# CaravanPi_V3.net
KiCad netlist of a schematic drawn in EAGLE
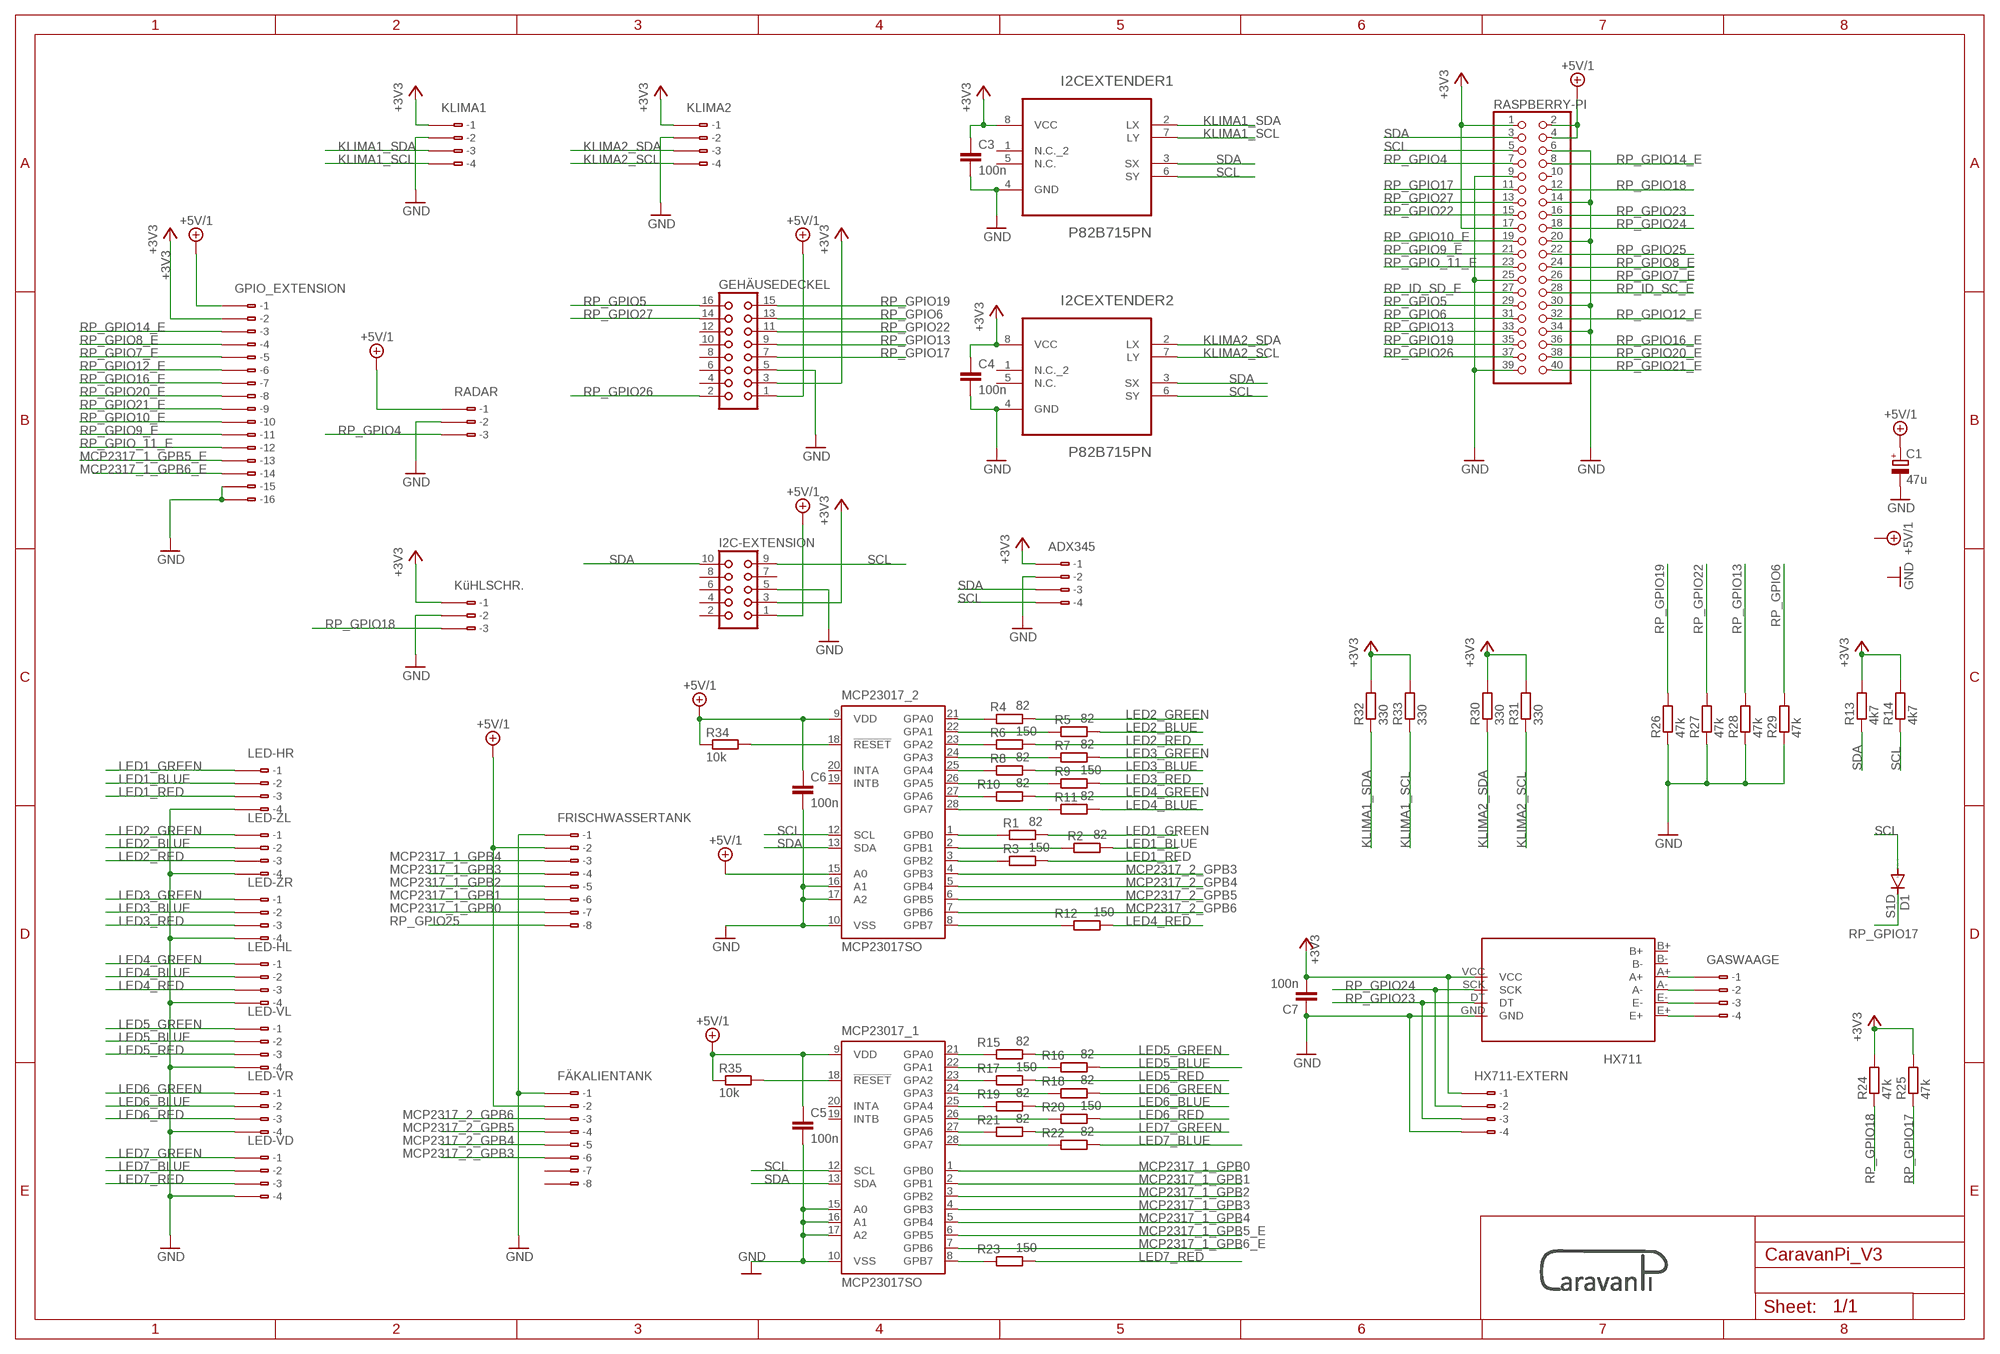
[diagram p0: schematic, sheet 1]

(export (version "E")
  (design (tool "Eeschema 10.0.6"))
  (components
    (comp (ref "ADX345")
      (value "233-404")
      (footprint "eagle-import:233-404")
      (libsource (lib "eagle-import") (part "233-404"))
    )
    (comp (ref "C1")
      (value "47u")
      (footprint "eagle-import:SMC_C")
      (libsource (lib "eagle-import") (part "CPOL-EUSMCC"))
    )
    (comp (ref "C3")
      (value "100n")
      (footprint "eagle-import:C1206")
      (libsource (lib "eagle-import") (part "C-EUC1206"))
    )
    (comp (ref "C4")
      (value "100n")
      (footprint "eagle-import:C1206")
      (libsource (lib "eagle-import") (part "C-EUC1206"))
    )
    (comp (ref "C5")
      (value "100n")
      (footprint "eagle-import:C1206")
      (libsource (lib "eagle-import") (part "C-EUC1206"))
    )
    (comp (ref "C6")
      (value "100n")
      (footprint "eagle-import:C1206")
      (libsource (lib "eagle-import") (part "C-EUC1206"))
    )
    (comp (ref "C7")
      (value "100n")
      (footprint "eagle-import:C1206")
      (libsource (lib "eagle-import") (part "C-EUC1206"))
    )
    (comp (ref "D1")
      (value "S1D")
      (footprint "eagle-import:DO214AC")
      (libsource (lib "eagle-import") (part "DIODE-DO214AC"))
    )
    (comp (ref "FRISCHWASSERTANK")
      (value "233-408")
      (footprint "eagle-import:233-408")
      (libsource (lib "eagle-import") (part "233-408"))
    )
    (comp (ref "FÄKALIENTANK")
      (value "233-408")
      (footprint "eagle-import:233-408")
      (libsource (lib "eagle-import") (part "233-408"))
    )
    (comp (ref "GASWAAGE")
      (value "233-404")
      (footprint "eagle-import:233-404")
      (libsource (lib "eagle-import") (part "233-404"))
    )
    (comp (ref "GEHÄUSEDECKEL")
      (value "CON16")
      (footprint "eagle-import:CON16")
      (libsource (lib "eagle-import") (part "CON16"))
    )
    (comp (ref "GPIO_EXTENSION")
      (value "233-516")
      (footprint "eagle-import:233-516")
      (fields (field (name "MF") "Wago Corporation") (field (name "MPN") "0233-0516"))
      (libsource (lib "eagle-import") (part "233-516"))
    )
    (comp (ref "HX711")
      (value "HX711A")
      (footprint "eagle-import:HX711")
      (libsource (lib "eagle-import") (part "HX711A"))
    )
    (comp (ref "HX711-EXTERN")
      (value "233-404")
      (footprint "eagle-import:233-404")
      (libsource (lib "eagle-import") (part "233-404"))
    )
    (comp (ref "I2C-EXTENSION")
      (value "CON10")
      (footprint "eagle-import:CON10")
      (libsource (lib "eagle-import") (part "CON10"))
    )
    (comp (ref "I2CEXTENDER1")
      (value "P82B715PN")
      (footprint "eagle-import:DIP254P762X420-8")
      (libsource (lib "eagle-import") (part "P82B715PN"))
    )
    (comp (ref "I2CEXTENDER2")
      (value "P82B715PN")
      (footprint "eagle-import:DIP254P762X420-8")
      (libsource (lib "eagle-import") (part "P82B715PN"))
    )
    (comp (ref "KLIMA1")
      (value "233-404")
      (footprint "eagle-import:233-404")
      (libsource (lib "eagle-import") (part "233-404"))
    )
    (comp (ref "KLIMA2")
      (value "233-404")
      (footprint "eagle-import:233-404")
      (libsource (lib "eagle-import") (part "233-404"))
    )
    (comp (ref "KüHLSCHR.")
      (value "233-403")
      (footprint "eagle-import:233-403")
      (libsource (lib "eagle-import") (part "233-403"))
    )
    (comp (ref "LED-HL")
      (value "233-504")
      (footprint "eagle-import:233-504")
      (fields (field (name "MF") "Wago Corporation") (field (name "MPN") "0233-0504"))
      (libsource (lib "eagle-import") (part "233-504"))
    )
    (comp (ref "LED-HR")
      (value "233-504")
      (footprint "eagle-import:233-504")
      (fields (field (name "MF") "Wago Corporation") (field (name "MPN") "0233-0504"))
      (libsource (lib "eagle-import") (part "233-504"))
    )
    (comp (ref "LED-VD")
      (value "233-504")
      (footprint "eagle-import:233-504")
      (fields (field (name "MF") "Wago Corporation") (field (name "MPN") "0233-0504"))
      (libsource (lib "eagle-import") (part "233-504"))
    )
    (comp (ref "LED-VL")
      (value "233-504")
      (footprint "eagle-import:233-504")
      (fields (field (name "MF") "Wago Corporation") (field (name "MPN") "0233-0504"))
      (libsource (lib "eagle-import") (part "233-504"))
    )
    (comp (ref "LED-VR")
      (value "233-504")
      (footprint "eagle-import:233-504")
      (fields (field (name "MF") "Wago Corporation") (field (name "MPN") "0233-0504"))
      (libsource (lib "eagle-import") (part "233-504"))
    )
    (comp (ref "LED-ZL")
      (value "233-504")
      (footprint "eagle-import:233-504")
      (fields (field (name "MF") "Wago Corporation") (field (name "MPN") "0233-0504"))
      (libsource (lib "eagle-import") (part "233-504"))
    )
    (comp (ref "LED-ZR")
      (value "233-504")
      (footprint "eagle-import:233-504")
      (fields (field (name "MF") "Wago Corporation") (field (name "MPN") "0233-0504"))
      (libsource (lib "eagle-import") (part "233-504"))
    )
    (comp (ref "MCP23017_1")
      (value "MCP23017SO")
      (footprint "eagle-import:SO28W")
      (libsource (lib "eagle-import") (part "MCP23017SO"))
    )
    (comp (ref "MCP23017_2")
      (value "MCP23017SO")
      (footprint "eagle-import:SO28W")
      (libsource (lib "eagle-import") (part "MCP23017SO"))
    )
    (comp (ref "R1")
      (value "82")
      (footprint "eagle-import:M1206")
      (libsource (lib "eagle-import") (part "R-EU_M1206"))
    )
    (comp (ref "R2")
      (value "82")
      (footprint "eagle-import:M1206")
      (libsource (lib "eagle-import") (part "R-EU_M1206"))
    )
    (comp (ref "R3")
      (value "150")
      (footprint "eagle-import:M1206")
      (libsource (lib "eagle-import") (part "R-EU_M1206"))
    )
    (comp (ref "R4")
      (value "82")
      (footprint "eagle-import:M1206")
      (libsource (lib "eagle-import") (part "R-EU_M1206"))
    )
    (comp (ref "R5")
      (value "82")
      (footprint "eagle-import:M1206")
      (libsource (lib "eagle-import") (part "R-EU_M1206"))
    )
    (comp (ref "R6")
      (value "150")
      (footprint "eagle-import:M1206")
      (libsource (lib "eagle-import") (part "R-EU_M1206"))
    )
    (comp (ref "R7")
      (value "82")
      (footprint "eagle-import:M1206")
      (libsource (lib "eagle-import") (part "R-EU_M1206"))
    )
    (comp (ref "R8")
      (value "82")
      (footprint "eagle-import:M1206")
      (libsource (lib "eagle-import") (part "R-EU_M1206"))
    )
    (comp (ref "R9")
      (value "150")
      (footprint "eagle-import:M1206")
      (libsource (lib "eagle-import") (part "R-EU_M1206"))
    )
    (comp (ref "R10")
      (value "82")
      (footprint "eagle-import:M1206")
      (libsource (lib "eagle-import") (part "R-EU_M1206"))
    )
    (comp (ref "R11")
      (value "82")
      (footprint "eagle-import:M1206")
      (libsource (lib "eagle-import") (part "R-EU_M1206"))
    )
    (comp (ref "R12")
      (value "150")
      (footprint "eagle-import:M1206")
      (libsource (lib "eagle-import") (part "R-EU_M1206"))
    )
    (comp (ref "R13")
      (value "4k7")
      (footprint "eagle-import:M1206")
      (libsource (lib "eagle-import") (part "R-EU_M1206"))
    )
    (comp (ref "R14")
      (value "4k7")
      (footprint "eagle-import:M1206")
      (libsource (lib "eagle-import") (part "R-EU_M1206"))
    )
    (comp (ref "R15")
      (value "82")
      (footprint "eagle-import:M1206")
      (libsource (lib "eagle-import") (part "R-EU_M1206"))
    )
    (comp (ref "R16")
      (value "82")
      (footprint "eagle-import:M1206")
      (libsource (lib "eagle-import") (part "R-EU_M1206"))
    )
    (comp (ref "R17")
      (value "150")
      (footprint "eagle-import:M1206")
      (libsource (lib "eagle-import") (part "R-EU_M1206"))
    )
    (comp (ref "R18")
      (value "82")
      (footprint "eagle-import:M1206")
      (libsource (lib "eagle-import") (part "R-EU_M1206"))
    )
    (comp (ref "R19")
      (value "82")
      (footprint "eagle-import:M1206")
      (libsource (lib "eagle-import") (part "R-EU_M1206"))
    )
    (comp (ref "R20")
      (value "150")
      (footprint "eagle-import:M1206")
      (libsource (lib "eagle-import") (part "R-EU_M1206"))
    )
    (comp (ref "R21")
      (value "82")
      (footprint "eagle-import:M1206")
      (libsource (lib "eagle-import") (part "R-EU_M1206"))
    )
    (comp (ref "R22")
      (value "82")
      (footprint "eagle-import:M1206")
      (libsource (lib "eagle-import") (part "R-EU_M1206"))
    )
    (comp (ref "R23")
      (value "150")
      (footprint "eagle-import:M1206")
      (libsource (lib "eagle-import") (part "R-EU_M1206"))
    )
    (comp (ref "R24")
      (value "47k")
      (footprint "eagle-import:M1206")
      (libsource (lib "eagle-import") (part "R-EU_M1206"))
    )
    (comp (ref "R25")
      (value "47k")
      (footprint "eagle-import:M1206")
      (libsource (lib "eagle-import") (part "R-EU_M1206"))
    )
    (comp (ref "R26")
      (value "47k")
      (footprint "eagle-import:M1206")
      (libsource (lib "eagle-import") (part "R-EU_M1206"))
    )
    (comp (ref "R27")
      (value "47k")
      (footprint "eagle-import:M1206")
      (libsource (lib "eagle-import") (part "R-EU_M1206"))
    )
    (comp (ref "R28")
      (value "47k")
      (footprint "eagle-import:M1206")
      (libsource (lib "eagle-import") (part "R-EU_M1206"))
    )
    (comp (ref "R29")
      (value "47k")
      (footprint "eagle-import:M1206")
      (libsource (lib "eagle-import") (part "R-EU_M1206"))
    )
    (comp (ref "R30")
      (value "330")
      (footprint "eagle-import:M1206")
      (libsource (lib "eagle-import") (part "R-EU_M1206"))
    )
    (comp (ref "R31")
      (value "330")
      (footprint "eagle-import:M1206")
      (libsource (lib "eagle-import") (part "R-EU_M1206"))
    )
    (comp (ref "R32")
      (value "330")
      (footprint "eagle-import:M1206")
      (libsource (lib "eagle-import") (part "R-EU_M1206"))
    )
    (comp (ref "R33")
      (value "330")
      (footprint "eagle-import:M1206")
      (libsource (lib "eagle-import") (part "R-EU_M1206"))
    )
    (comp (ref "R34")
      (value "10k")
      (footprint "eagle-import:M1206")
      (libsource (lib "eagle-import") (part "R-EU_M1206"))
    )
    (comp (ref "R35")
      (value "10k")
      (footprint "eagle-import:M1206")
      (libsource (lib "eagle-import") (part "R-EU_M1206"))
    )
    (comp (ref "RADAR")
      (value "233-403")
      (footprint "eagle-import:233-403")
      (libsource (lib "eagle-import") (part "233-403"))
    )
    (comp (ref "RASPBERRY-PI")
      (value "PINHD-2X20")
      (footprint "eagle-import:2X20")
      (libsource (lib "eagle-import") (part "PINHD-2X20"))
    )
    (comp (ref "U$1")
      (value "CARAVAN_PI_LOGO")
      (footprint "eagle-import:CARAVAN_PI_LOGO")
      (libsource (lib "eagle-import") (part "CARAVAN_PI_LOGO"))
    )
  )
  (nets
    (net (code "1") (name "+3V3") (class "Default")
      (node (ref "ADX345") (pin "B1") (pinfunction "B-1_B1") (pintype "passive"))
      (node (ref "C3") (pin "1") (pinfunction "1_1") (pintype "passive"))
      (node (ref "C4") (pin "1") (pinfunction "1_1") (pintype "passive"))
      (node (ref "C7") (pin "2") (pinfunction "2_2") (pintype "passive"))
      (node (ref "GEHÄUSEDECKEL") (pin "3") (pinfunction "3_3") (pintype "passive"))
      (node (ref "GPIO_EXTENSION") (pin "B2") (pinfunction "B-2_B2") (pintype "passive"))
      (node (ref "HX711") (pin "VCC") (pinfunction "VCC_VCC") (pintype "bidirectional"))
      (node (ref "HX711-EXTERN") (pin "B1") (pinfunction "B-1_B1") (pintype "passive"))
      (node (ref "I2C-EXTENSION") (pin "3") (pinfunction "3_3") (pintype "passive"))
      (node (ref "I2CEXTENDER1") (pin "8") (pinfunction "VCC_8") (pintype "power_in"))
      (node (ref "I2CEXTENDER2") (pin "8") (pinfunction "VCC_8") (pintype "power_in"))
      (node (ref "KLIMA1") (pin "B1") (pinfunction "B-1_B1") (pintype "passive"))
      (node (ref "KLIMA2") (pin "B1") (pinfunction "B-1_B1") (pintype "passive"))
      (node (ref "KüHLSCHR.") (pin "B1") (pinfunction "B-1_B1") (pintype "passive"))
      (node (ref "R13") (pin "2") (pinfunction "2_2") (pintype "passive"))
      (node (ref "R14") (pin "2") (pinfunction "2_2") (pintype "passive"))
      (node (ref "R24") (pin "2") (pinfunction "2_2") (pintype "passive"))
      (node (ref "R25") (pin "2") (pinfunction "2_2") (pintype "passive"))
      (node (ref "R30") (pin "2") (pinfunction "2_2") (pintype "passive"))
      (node (ref "R31") (pin "2") (pinfunction "2_2") (pintype "passive"))
      (node (ref "R32") (pin "2") (pinfunction "2_2") (pintype "passive"))
      (node (ref "R33") (pin "2") (pinfunction "2_2") (pintype "passive"))
      (node (ref "RASPBERRY-PI") (pin "1") (pinfunction "1_1") (pintype "passive"))
      (node (ref "RASPBERRY-PI") (pin "17") (pinfunction "17_17") (pintype "passive"))
    )
    (net (code "2") (name "+5V{slash}1") (class "Default")
      (node (ref "C1") (pin "+") (pinfunction "+_+") (pintype "passive"))
      (node (ref "C5") (pin "1") (pinfunction "1_1") (pintype "passive"))
      (node (ref "C6") (pin "1") (pinfunction "1_1") (pintype "passive"))
      (node (ref "FRISCHWASSERTANK") (pin "B2") (pinfunction "B-2_B2") (pintype "passive"))
      (node (ref "FÄKALIENTANK") (pin "B2") (pinfunction "B-2_B2") (pintype "passive"))
      (node (ref "GEHÄUSEDECKEL") (pin "1") (pinfunction "1_1") (pintype "passive"))
      (node (ref "GPIO_EXTENSION") (pin "B1") (pinfunction "B-1_B1") (pintype "passive"))
      (node (ref "I2C-EXTENSION") (pin "1") (pinfunction "1_1") (pintype "passive"))
      (node (ref "MCP23017_1") (pin "9") (pinfunction "VDD_9") (pintype "power_in"))
      (node (ref "MCP23017_2") (pin "15") (pinfunction "A0_15") (pintype "input"))
      (node (ref "MCP23017_2") (pin "9") (pinfunction "VDD_9") (pintype "power_in"))
      (node (ref "R34") (pin "1") (pinfunction "1_1") (pintype "passive"))
      (node (ref "R35") (pin "1") (pinfunction "1_1") (pintype "passive"))
      (node (ref "RADAR") (pin "B1") (pinfunction "B-1_B1") (pintype "passive"))
      (node (ref "RASPBERRY-PI") (pin "2") (pinfunction "2_2") (pintype "passive"))
      (node (ref "RASPBERRY-PI") (pin "4") (pinfunction "4_4") (pintype "passive"))
    )
    (net (code "3") (name "/KLIMA1_SCL") (class "Default")
      (node (ref "I2CEXTENDER1") (pin "7") (pinfunction "LY_7") (pintype "bidirectional"))
      (node (ref "KLIMA1") (pin "B4") (pinfunction "B-4_B4") (pintype "passive"))
      (node (ref "R33") (pin "1") (pinfunction "1_1") (pintype "passive"))
    )
    (net (code "4") (name "/KLIMA1_SDA") (class "Default")
      (node (ref "I2CEXTENDER1") (pin "2") (pinfunction "LX_2") (pintype "bidirectional"))
      (node (ref "KLIMA1") (pin "B3") (pinfunction "B-3_B3") (pintype "passive"))
      (node (ref "R32") (pin "1") (pinfunction "1_1") (pintype "passive"))
    )
    (net (code "5") (name "/KLIMA2_SCL") (class "Default")
      (node (ref "I2CEXTENDER2") (pin "7") (pinfunction "LY_7") (pintype "bidirectional"))
      (node (ref "KLIMA2") (pin "B4") (pinfunction "B-4_B4") (pintype "passive"))
      (node (ref "R31") (pin "1") (pinfunction "1_1") (pintype "passive"))
    )
    (net (code "6") (name "/KLIMA2_SDA") (class "Default")
      (node (ref "I2CEXTENDER2") (pin "2") (pinfunction "LX_2") (pintype "bidirectional"))
      (node (ref "KLIMA2") (pin "B3") (pinfunction "B-3_B3") (pintype "passive"))
      (node (ref "R30") (pin "1") (pinfunction "1_1") (pintype "passive"))
    )
    (net (code "7") (name "/LED1_BLUE") (class "Default")
      (node (ref "LED-HR") (pin "B2") (pinfunction "B-2_B2") (pintype "passive"))
      (node (ref "R2") (pin "2") (pinfunction "2_2") (pintype "passive"))
    )
    (net (code "8") (name "/LED1_GREEN") (class "Default")
      (node (ref "LED-HR") (pin "B1") (pinfunction "B-1_B1") (pintype "passive"))
      (node (ref "R1") (pin "2") (pinfunction "2_2") (pintype "passive"))
    )
    (net (code "9") (name "/LED1_RED") (class "Default")
      (node (ref "LED-HR") (pin "B3") (pinfunction "B-3_B3") (pintype "passive"))
      (node (ref "R3") (pin "2") (pinfunction "2_2") (pintype "passive"))
    )
    (net (code "10") (name "/LED2_BLUE") (class "Default")
      (node (ref "LED-ZL") (pin "B2") (pinfunction "B-2_B2") (pintype "passive"))
      (node (ref "R5") (pin "2") (pinfunction "2_2") (pintype "passive"))
    )
    (net (code "11") (name "/LED2_GREEN") (class "Default")
      (node (ref "LED-ZL") (pin "B1") (pinfunction "B-1_B1") (pintype "passive"))
      (node (ref "R4") (pin "2") (pinfunction "2_2") (pintype "passive"))
    )
    (net (code "12") (name "/LED2_RED") (class "Default")
      (node (ref "LED-ZL") (pin "B3") (pinfunction "B-3_B3") (pintype "passive"))
      (node (ref "R6") (pin "2") (pinfunction "2_2") (pintype "passive"))
    )
    (net (code "13") (name "/LED3_BLUE") (class "Default")
      (node (ref "LED-ZR") (pin "B2") (pinfunction "B-2_B2") (pintype "passive"))
      (node (ref "R8") (pin "2") (pinfunction "2_2") (pintype "passive"))
    )
    (net (code "14") (name "/LED3_GREEN") (class "Default")
      (node (ref "LED-ZR") (pin "B1") (pinfunction "B-1_B1") (pintype "passive"))
      (node (ref "R7") (pin "2") (pinfunction "2_2") (pintype "passive"))
    )
    (net (code "15") (name "/LED3_RED") (class "Default")
      (node (ref "LED-ZR") (pin "B3") (pinfunction "B-3_B3") (pintype "passive"))
      (node (ref "R9") (pin "2") (pinfunction "2_2") (pintype "passive"))
    )
    (net (code "16") (name "/LED4_BLUE") (class "Default")
      (node (ref "LED-HL") (pin "B2") (pinfunction "B-2_B2") (pintype "passive"))
      (node (ref "R11") (pin "2") (pinfunction "2_2") (pintype "passive"))
    )
    (net (code "17") (name "/LED4_GREEN") (class "Default")
      (node (ref "LED-HL") (pin "B1") (pinfunction "B-1_B1") (pintype "passive"))
      (node (ref "R10") (pin "2") (pinfunction "2_2") (pintype "passive"))
    )
    (net (code "18") (name "/LED4_RED") (class "Default")
      (node (ref "LED-HL") (pin "B3") (pinfunction "B-3_B3") (pintype "passive"))
      (node (ref "R12") (pin "2") (pinfunction "2_2") (pintype "passive"))
    )
    (net (code "19") (name "/LED5_BLUE") (class "Default")
      (node (ref "LED-VL") (pin "B2") (pinfunction "B-2_B2") (pintype "passive"))
      (node (ref "R16") (pin "2") (pinfunction "2_2") (pintype "passive"))
    )
    (net (code "20") (name "/LED5_GREEN") (class "Default")
      (node (ref "LED-VL") (pin "B1") (pinfunction "B-1_B1") (pintype "passive"))
      (node (ref "R15") (pin "2") (pinfunction "2_2") (pintype "passive"))
    )
    (net (code "21") (name "/LED5_RED") (class "Default")
      (node (ref "LED-VL") (pin "B3") (pinfunction "B-3_B3") (pintype "passive"))
      (node (ref "R17") (pin "2") (pinfunction "2_2") (pintype "passive"))
    )
    (net (code "22") (name "/LED6_BLUE") (class "Default")
      (node (ref "LED-VR") (pin "B2") (pinfunction "B-2_B2") (pintype "passive"))
      (node (ref "R19") (pin "2") (pinfunction "2_2") (pintype "passive"))
    )
    (net (code "23") (name "/LED6_GREEN") (class "Default")
      (node (ref "LED-VR") (pin "B1") (pinfunction "B-1_B1") (pintype "passive"))
      (node (ref "R18") (pin "2") (pinfunction "2_2") (pintype "passive"))
    )
    (net (code "24") (name "/LED6_RED") (class "Default")
      (node (ref "LED-VR") (pin "B3") (pinfunction "B-3_B3") (pintype "passive"))
      (node (ref "R20") (pin "2") (pinfunction "2_2") (pintype "passive"))
    )
    (net (code "25") (name "/LED7_BLUE") (class "Default")
      (node (ref "LED-VD") (pin "B2") (pinfunction "B-2_B2") (pintype "passive"))
      (node (ref "R22") (pin "2") (pinfunction "2_2") (pintype "passive"))
    )
    (net (code "26") (name "/LED7_GREEN") (class "Default")
      (node (ref "LED-VD") (pin "B1") (pinfunction "B-1_B1") (pintype "passive"))
      (node (ref "R21") (pin "2") (pinfunction "2_2") (pintype "passive"))
    )
    (net (code "27") (name "/LED7_RED") (class "Default")
      (node (ref "LED-VD") (pin "B3") (pinfunction "B-3_B3") (pintype "passive"))
      (node (ref "R23") (pin "2") (pinfunction "2_2") (pintype "passive"))
    )
    (net (code "28") (name "/MCP2317_1_GPB0") (class "Default")
      (node (ref "FRISCHWASSERTANK") (pin "B7") (pinfunction "B-7_B7") (pintype "passive"))
      (node (ref "MCP23017_1") (pin "1") (pinfunction "GPB0_1") (pintype "bidirectional"))
    )
    (net (code "29") (name "/MCP2317_1_GPB1") (class "Default")
      (node (ref "FRISCHWASSERTANK") (pin "B6") (pinfunction "B-6_B6") (pintype "passive"))
      (node (ref "MCP23017_1") (pin "2") (pinfunction "GPB1_2") (pintype "bidirectional"))
    )
    (net (code "30") (name "/MCP2317_1_GPB2") (class "Default")
      (node (ref "FRISCHWASSERTANK") (pin "B5") (pinfunction "B-5_B5") (pintype "passive"))
      (node (ref "MCP23017_1") (pin "3") (pinfunction "GPB2_3") (pintype "bidirectional"))
    )
    (net (code "31") (name "/MCP2317_1_GPB3") (class "Default")
      (node (ref "FRISCHWASSERTANK") (pin "B4") (pinfunction "B-4_B4") (pintype "passive"))
      (node (ref "MCP23017_1") (pin "4") (pinfunction "GPB3_4") (pintype "bidirectional"))
    )
    (net (code "32") (name "/MCP2317_1_GPB4") (class "Default")
      (node (ref "FRISCHWASSERTANK") (pin "B3") (pinfunction "B-3_B3") (pintype "passive"))
      (node (ref "MCP23017_1") (pin "5") (pinfunction "GPB4_5") (pintype "bidirectional"))
    )
    (net (code "33") (name "/MCP2317_1_GPB5_E") (class "Default")
      (node (ref "GPIO_EXTENSION") (pin "B13") (pinfunction "B-13_B13") (pintype "passive"))
      (node (ref "MCP23017_1") (pin "6") (pinfunction "GPB5_6") (pintype "bidirectional"))
    )
    (net (code "34") (name "/MCP2317_1_GPB6_E") (class "Default")
      (node (ref "GPIO_EXTENSION") (pin "B14") (pinfunction "B-14_B14") (pintype "passive"))
      (node (ref "MCP23017_1") (pin "7") (pinfunction "GPB6_7") (pintype "bidirectional"))
    )
    (net (code "35") (name "/MCP2317_2_GPB3") (class "Default")
      (node (ref "FÄKALIENTANK") (pin "B6") (pinfunction "B-6_B6") (pintype "passive"))
      (node (ref "MCP23017_2") (pin "4") (pinfunction "GPB3_4") (pintype "bidirectional"))
    )
    (net (code "36") (name "/MCP2317_2_GPB4") (class "Default")
      (node (ref "FÄKALIENTANK") (pin "B5") (pinfunction "B-5_B5") (pintype "passive"))
      (node (ref "MCP23017_2") (pin "5") (pinfunction "GPB4_5") (pintype "bidirectional"))
    )
    (net (code "37") (name "/MCP2317_2_GPB5") (class "Default")
      (node (ref "FÄKALIENTANK") (pin "B4") (pinfunction "B-4_B4") (pintype "passive"))
      (node (ref "MCP23017_2") (pin "6") (pinfunction "GPB5_6") (pintype "bidirectional"))
    )
    (net (code "38") (name "/MCP2317_2_GPB6") (class "Default")
      (node (ref "FÄKALIENTANK") (pin "B3") (pinfunction "B-3_B3") (pintype "passive"))
      (node (ref "MCP23017_2") (pin "7") (pinfunction "GPB6_7") (pintype "bidirectional"))
    )
    (net (code "39") (name "/RP_GPIO4") (class "Default")
      (node (ref "RADAR") (pin "B3") (pinfunction "B-3_B3") (pintype "passive"))
      (node (ref "RASPBERRY-PI") (pin "7") (pinfunction "7_7") (pintype "passive"))
    )
    (net (code "40") (name "/RP_GPIO5") (class "Default")
      (node (ref "GEHÄUSEDECKEL") (pin "16") (pinfunction "16_16") (pintype "passive"))
      (node (ref "RASPBERRY-PI") (pin "29") (pinfunction "29_29") (pintype "passive"))
    )
    (net (code "41") (name "/RP_GPIO6") (class "Default")
      (node (ref "GEHÄUSEDECKEL") (pin "13") (pinfunction "13_13") (pintype "passive"))
      (node (ref "R29") (pin "2") (pinfunction "2_2") (pintype "passive"))
      (node (ref "RASPBERRY-PI") (pin "31") (pinfunction "31_31") (pintype "passive"))
    )
    (net (code "42") (name "/RP_GPIO7_E") (class "Default")
      (node (ref "GPIO_EXTENSION") (pin "B5") (pinfunction "B-5_B5") (pintype "passive"))
      (node (ref "RASPBERRY-PI") (pin "26") (pinfunction "26_26") (pintype "passive"))
    )
    (net (code "43") (name "/RP_GPIO8_E") (class "Default")
      (node (ref "GPIO_EXTENSION") (pin "B4") (pinfunction "B-4_B4") (pintype "passive"))
      (node (ref "RASPBERRY-PI") (pin "24") (pinfunction "24_24") (pintype "passive"))
    )
    (net (code "44") (name "/RP_GPIO9_E") (class "Default")
      (node (ref "GPIO_EXTENSION") (pin "B11") (pinfunction "B-11_B11") (pintype "passive"))
      (node (ref "RASPBERRY-PI") (pin "21") (pinfunction "21_21") (pintype "passive"))
    )
    (net (code "45") (name "/RP_GPIO10_E") (class "Default")
      (node (ref "GPIO_EXTENSION") (pin "B10") (pinfunction "B-10_B10") (pintype "passive"))
      (node (ref "RASPBERRY-PI") (pin "19") (pinfunction "19_19") (pintype "passive"))
    )
    (net (code "46") (name "/RP_GPIO12_E") (class "Default")
      (node (ref "GPIO_EXTENSION") (pin "B6") (pinfunction "B-6_B6") (pintype "passive"))
      (node (ref "RASPBERRY-PI") (pin "32") (pinfunction "32_32") (pintype "passive"))
    )
    (net (code "47") (name "/RP_GPIO13") (class "Default")
      (node (ref "GEHÄUSEDECKEL") (pin "9") (pinfunction "9_9") (pintype "passive"))
      (node (ref "R28") (pin "2") (pinfunction "2_2") (pintype "passive"))
      (node (ref "RASPBERRY-PI") (pin "33") (pinfunction "33_33") (pintype "passive"))
    )
    (net (code "48") (name "/RP_GPIO14_E") (class "Default")
      (node (ref "GPIO_EXTENSION") (pin "B3") (pinfunction "B-3_B3") (pintype "passive"))
      (node (ref "RASPBERRY-PI") (pin "8") (pinfunction "8_8") (pintype "passive"))
    )
    (net (code "49") (name "/RP_GPIO16_E") (class "Default")
      (node (ref "GPIO_EXTENSION") (pin "B7") (pinfunction "B-7_B7") (pintype "passive"))
      (node (ref "RASPBERRY-PI") (pin "36") (pinfunction "36_36") (pintype "passive"))
    )
    (net (code "50") (name "/RP_GPIO17") (class "Default")
      (node (ref "D1") (pin "C") (pinfunction "C_C") (pintype "passive"))
      (node (ref "GEHÄUSEDECKEL") (pin "7") (pinfunction "7_7") (pintype "passive"))
      (node (ref "R25") (pin "1") (pinfunction "1_1") (pintype "passive"))
      (node (ref "RASPBERRY-PI") (pin "11") (pinfunction "11_11") (pintype "passive"))
    )
    (net (code "51") (name "/RP_GPIO18") (class "Default")
      (node (ref "KüHLSCHR.") (pin "B3") (pinfunction "B-3_B3") (pintype "passive"))
      (node (ref "R24") (pin "1") (pinfunction "1_1") (pintype "passive"))
      (node (ref "RASPBERRY-PI") (pin "12") (pinfunction "12_12") (pintype "passive"))
    )
    (net (code "52") (name "/RP_GPIO19") (class "Default")
      (node (ref "GEHÄUSEDECKEL") (pin "15") (pinfunction "15_15") (pintype "passive"))
      (node (ref "R26") (pin "2") (pinfunction "2_2") (pintype "passive"))
      (node (ref "RASPBERRY-PI") (pin "35") (pinfunction "35_35") (pintype "passive"))
    )
    (net (code "53") (name "/RP_GPIO20_E") (class "Default")
      (node (ref "GPIO_EXTENSION") (pin "B8") (pinfunction "B-8_B8") (pintype "passive"))
      (node (ref "RASPBERRY-PI") (pin "38") (pinfunction "38_38") (pintype "passive"))
    )
    (net (code "54") (name "/RP_GPIO21_E") (class "Default")
      (node (ref "GPIO_EXTENSION") (pin "B9") (pinfunction "B-9_B9") (pintype "passive"))
      (node (ref "RASPBERRY-PI") (pin "40") (pinfunction "40_40") (pintype "passive"))
    )
    (net (code "55") (name "/RP_GPIO22") (class "Default")
      (node (ref "GEHÄUSEDECKEL") (pin "11") (pinfunction "11_11") (pintype "passive"))
      (node (ref "R27") (pin "2") (pinfunction "2_2") (pintype "passive"))
      (node (ref "RASPBERRY-PI") (pin "15") (pinfunction "15_15") (pintype "passive"))
    )
    (net (code "56") (name "/RP_GPIO23") (class "Default")
      (node (ref "HX711") (pin "DT") (pinfunction "DT_DT") (pintype "bidirectional"))
      (node (ref "HX711-EXTERN") (pin "B3") (pinfunction "B-3_B3") (pintype "passive"))
      (node (ref "RASPBERRY-PI") (pin "16") (pinfunction "16_16") (pintype "passive"))
    )
    (net (code "57") (name "/RP_GPIO24") (class "Default")
      (node (ref "HX711") (pin "SCK") (pinfunction "SCK_SCK") (pintype "bidirectional"))
      (node (ref "HX711-EXTERN") (pin "B2") (pinfunction "B-2_B2") (pintype "passive"))
      (node (ref "RASPBERRY-PI") (pin "18") (pinfunction "18_18") (pintype "passive"))
    )
    (net (code "58") (name "/RP_GPIO25") (class "Default")
      (node (ref "FRISCHWASSERTANK") (pin "B8") (pinfunction "B-8_B8") (pintype "passive"))
      (node (ref "RASPBERRY-PI") (pin "22") (pinfunction "22_22") (pintype "passive"))
    )
    (net (code "59") (name "/RP_GPIO26") (class "Default")
      (node (ref "GEHÄUSEDECKEL") (pin "2") (pinfunction "2_2") (pintype "passive"))
      (node (ref "RASPBERRY-PI") (pin "37") (pinfunction "37_37") (pintype "passive"))
    )
    (net (code "60") (name "/RP_GPIO27") (class "Default")
      (node (ref "GEHÄUSEDECKEL") (pin "14") (pinfunction "14_14") (pintype "passive"))
      (node (ref "RASPBERRY-PI") (pin "13") (pinfunction "13_13") (pintype "passive"))
    )
    (net (code "61") (name "/RP_GPIO_11_E") (class "Default")
      (node (ref "GPIO_EXTENSION") (pin "B12") (pinfunction "B-12_B12") (pintype "passive"))
      (node (ref "RASPBERRY-PI") (pin "23") (pinfunction "23_23") (pintype "passive"))
    )
    (net (code "62") (name "/RP_ID_SC_E") (class "Default")
      (node (ref "RASPBERRY-PI") (pin "28") (pinfunction "28_28") (pintype "passive"))
    )
    (net (code "63") (name "/RP_ID_SD_E") (class "Default")
      (node (ref "RASPBERRY-PI") (pin "27") (pinfunction "27_27") (pintype "passive"))
    )
    (net (code "64") (name "/SCL") (class "Default")
      (node (ref "ADX345") (pin "B4") (pinfunction "B-4_B4") (pintype "passive"))
      (node (ref "D1") (pin "A") (pinfunction "A_A") (pintype "passive"))
      (node (ref "I2C-EXTENSION") (pin "9") (pinfunction "9_9") (pintype "passive"))
      (node (ref "I2CEXTENDER1") (pin "6") (pinfunction "SY_6") (pintype "bidirectional"))
      (node (ref "I2CEXTENDER2") (pin "6") (pinfunction "SY_6") (pintype "bidirectional"))
      (node (ref "MCP23017_1") (pin "12") (pinfunction "SCL_12") (pintype "input"))
      (node (ref "MCP23017_2") (pin "12") (pinfunction "SCL_12") (pintype "input"))
      (node (ref "R14") (pin "1") (pinfunction "1_1") (pintype "passive"))
      (node (ref "RASPBERRY-PI") (pin "5") (pinfunction "5_5") (pintype "passive"))
    )
    (net (code "65") (name "/SDA") (class "Default")
      (node (ref "ADX345") (pin "B3") (pinfunction "B-3_B3") (pintype "passive"))
      (node (ref "I2C-EXTENSION") (pin "10") (pinfunction "10_10") (pintype "passive"))
      (node (ref "I2CEXTENDER1") (pin "3") (pinfunction "SX_3") (pintype "bidirectional"))
      (node (ref "I2CEXTENDER2") (pin "3") (pinfunction "SX_3") (pintype "bidirectional"))
      (node (ref "MCP23017_1") (pin "13") (pinfunction "SDA_13") (pintype "bidirectional"))
      (node (ref "MCP23017_2") (pin "13") (pinfunction "SDA_13") (pintype "bidirectional"))
      (node (ref "R13") (pin "1") (pinfunction "1_1") (pintype "passive"))
      (node (ref "RASPBERRY-PI") (pin "3") (pinfunction "3_3") (pintype "passive"))
    )
    (net (code "66") (name "GND") (class "Default")
      (node (ref "ADX345") (pin "B2") (pinfunction "B-2_B2") (pintype "passive"))
      (node (ref "C1") (pin "-") (pinfunction "-_-") (pintype "passive"))
      (node (ref "C3") (pin "2") (pinfunction "2_2") (pintype "passive"))
      (node (ref "C4") (pin "2") (pinfunction "2_2") (pintype "passive"))
      (node (ref "C5") (pin "2") (pinfunction "2_2") (pintype "passive"))
      (node (ref "C6") (pin "2") (pinfunction "2_2") (pintype "passive"))
      (node (ref "C7") (pin "1") (pinfunction "1_1") (pintype "passive"))
      (node (ref "FRISCHWASSERTANK") (pin "B1") (pinfunction "B-1_B1") (pintype "passive"))
      (node (ref "FÄKALIENTANK") (pin "B1") (pinfunction "B-1_B1") (pintype "passive"))
      (node (ref "GEHÄUSEDECKEL") (pin "5") (pinfunction "5_5") (pintype "passive"))
      (node (ref "GPIO_EXTENSION") (pin "B15") (pinfunction "B-15_B15") (pintype "passive"))
      (node (ref "GPIO_EXTENSION") (pin "B16") (pinfunction "B-16_B16") (pintype "passive"))
      (node (ref "HX711") (pin "GND") (pinfunction "GND_GND") (pintype "bidirectional"))
      (node (ref "HX711-EXTERN") (pin "B4") (pinfunction "B-4_B4") (pintype "passive"))
      (node (ref "I2C-EXTENSION") (pin "5") (pinfunction "5_5") (pintype "passive"))
      (node (ref "I2CEXTENDER1") (pin "4") (pinfunction "GND_4") (pintype "passive"))
      (node (ref "I2CEXTENDER2") (pin "4") (pinfunction "GND_4") (pintype "passive"))
      (node (ref "KLIMA1") (pin "B2") (pinfunction "B-2_B2") (pintype "passive"))
      (node (ref "KLIMA2") (pin "B2") (pinfunction "B-2_B2") (pintype "passive"))
      (node (ref "KüHLSCHR.") (pin "B2") (pinfunction "B-2_B2") (pintype "passive"))
      (node (ref "LED-HL") (pin "B4") (pinfunction "B-4_B4") (pintype "passive"))
      (node (ref "LED-HR") (pin "B4") (pinfunction "B-4_B4") (pintype "passive"))
      (node (ref "LED-VD") (pin "B4") (pinfunction "B-4_B4") (pintype "passive"))
      (node (ref "LED-VL") (pin "B4") (pinfunction "B-4_B4") (pintype "passive"))
      (node (ref "LED-VR") (pin "B4") (pinfunction "B-4_B4") (pintype "passive"))
      (node (ref "LED-ZL") (pin "B4") (pinfunction "B-4_B4") (pintype "passive"))
      (node (ref "LED-ZR") (pin "B4") (pinfunction "B-4_B4") (pintype "passive"))
      (node (ref "MCP23017_1") (pin "10") (pinfunction "VSS_10") (pintype "power_in"))
      (node (ref "MCP23017_1") (pin "15") (pinfunction "A0_15") (pintype "input"))
      (node (ref "MCP23017_1") (pin "16") (pinfunction "A1_16") (pintype "input"))
      (node (ref "MCP23017_1") (pin "17") (pinfunction "A2_17") (pintype "input"))
      (node (ref "MCP23017_2") (pin "10") (pinfunction "VSS_10") (pintype "power_in"))
      (node (ref "MCP23017_2") (pin "16") (pinfunction "A1_16") (pintype "input"))
      (node (ref "MCP23017_2") (pin "17") (pinfunction "A2_17") (pintype "input"))
      (node (ref "R26") (pin "1") (pinfunction "1_1") (pintype "passive"))
      (node (ref "R27") (pin "1") (pinfunction "1_1") (pintype "passive"))
      (node (ref "R28") (pin "1") (pinfunction "1_1") (pintype "passive"))
      (node (ref "R29") (pin "1") (pinfunction "1_1") (pintype "passive"))
      (node (ref "RADAR") (pin "B2") (pinfunction "B-2_B2") (pintype "passive"))
      (node (ref "RASPBERRY-PI") (pin "14") (pinfunction "14_14") (pintype "passive"))
      (node (ref "RASPBERRY-PI") (pin "20") (pinfunction "20_20") (pintype "passive"))
      (node (ref "RASPBERRY-PI") (pin "25") (pinfunction "25_25") (pintype "passive"))
      (node (ref "RASPBERRY-PI") (pin "30") (pinfunction "30_30") (pintype "passive"))
      (node (ref "RASPBERRY-PI") (pin "34") (pinfunction "34_34") (pintype "passive"))
      (node (ref "RASPBERRY-PI") (pin "39") (pinfunction "39_39") (pintype "passive"))
      (node (ref "RASPBERRY-PI") (pin "6") (pinfunction "6_6") (pintype "passive"))
      (node (ref "RASPBERRY-PI") (pin "9") (pinfunction "9_9") (pintype "passive"))
    )
    (net (code "67") (name "Net-(GASWAAGE-B-1)") (class "Default")
      (node (ref "GASWAAGE") (pin "B1") (pinfunction "B-1_B1") (pintype "passive"))
      (node (ref "HX711") (pin "A+") (pinfunction "A+_A+") (pintype "bidirectional"))
    )
    (net (code "68") (name "Net-(GASWAAGE-B-2)") (class "Default")
      (node (ref "GASWAAGE") (pin "B2") (pinfunction "B-2_B2") (pintype "passive"))
      (node (ref "HX711") (pin "A-") (pinfunction "A-_A-") (pintype "bidirectional"))
    )
    (net (code "69") (name "Net-(GASWAAGE-B-3)") (class "Default")
      (node (ref "GASWAAGE") (pin "B3") (pinfunction "B-3_B3") (pintype "passive"))
      (node (ref "HX711") (pin "E-") (pinfunction "E-_E-") (pintype "bidirectional"))
    )
    (net (code "70") (name "Net-(GASWAAGE-B-4)") (class "Default")
      (node (ref "GASWAAGE") (pin "B4") (pinfunction "B-4_B4") (pintype "passive"))
      (node (ref "HX711") (pin "E+") (pinfunction "E+_E+") (pintype "bidirectional"))
    )
    (net (code "71") (name "Net-(MCP23017_1-GPA0)") (class "Default")
      (node (ref "MCP23017_1") (pin "21") (pinfunction "GPA0_21") (pintype "bidirectional"))
      (node (ref "R15") (pin "1") (pinfunction "1_1") (pintype "passive"))
    )
    (net (code "72") (name "Net-(MCP23017_1-GPA1)") (class "Default")
      (node (ref "MCP23017_1") (pin "22") (pinfunction "GPA1_22") (pintype "bidirectional"))
      (node (ref "R16") (pin "1") (pinfunction "1_1") (pintype "passive"))
    )
    (net (code "73") (name "Net-(MCP23017_1-GPA2)") (class "Default")
      (node (ref "MCP23017_1") (pin "23") (pinfunction "GPA2_23") (pintype "bidirectional"))
      (node (ref "R17") (pin "1") (pinfunction "1_1") (pintype "passive"))
    )
    (net (code "74") (name "Net-(MCP23017_1-GPA3)") (class "Default")
      (node (ref "MCP23017_1") (pin "24") (pinfunction "GPA3_24") (pintype "bidirectional"))
      (node (ref "R18") (pin "1") (pinfunction "1_1") (pintype "passive"))
    )
    (net (code "75") (name "Net-(MCP23017_1-GPA4)") (class "Default")
      (node (ref "MCP23017_1") (pin "25") (pinfunction "GPA4_25") (pintype "bidirectional"))
      (node (ref "R19") (pin "1") (pinfunction "1_1") (pintype "passive"))
    )
    (net (code "76") (name "Net-(MCP23017_1-GPA5)") (class "Default")
      (node (ref "MCP23017_1") (pin "26") (pinfunction "GPA5_26") (pintype "bidirectional"))
      (node (ref "R20") (pin "1") (pinfunction "1_1") (pintype "passive"))
    )
    (net (code "77") (name "Net-(MCP23017_1-GPA6)") (class "Default")
      (node (ref "MCP23017_1") (pin "27") (pinfunction "GPA6_27") (pintype "bidirectional"))
      (node (ref "R21") (pin "1") (pinfunction "1_1") (pintype "passive"))
    )
    (net (code "78") (name "Net-(MCP23017_1-GPA7)") (class "Default")
      (node (ref "MCP23017_1") (pin "28") (pinfunction "GPA7_28") (pintype "bidirectional"))
      (node (ref "R22") (pin "1") (pinfunction "1_1") (pintype "passive"))
    )
    (net (code "79") (name "Net-(MCP23017_1-GPB7)") (class "Default")
      (node (ref "MCP23017_1") (pin "8") (pinfunction "GPB7_8") (pintype "bidirectional"))
      (node (ref "R23") (pin "1") (pinfunction "1_1") (pintype "passive"))
    )
    (net (code "80") (name "Net-(MCP23017_1-~{RESET})") (class "Default")
      (node (ref "MCP23017_1") (pin "18") (pinfunction "~{RESET}_18") (pintype "input"))
      (node (ref "R35") (pin "2") (pinfunction "2_2") (pintype "passive"))
    )
    (net (code "81") (name "Net-(MCP23017_2-GPA0)") (class "Default")
      (node (ref "MCP23017_2") (pin "21") (pinfunction "GPA0_21") (pintype "bidirectional"))
      (node (ref "R4") (pin "1") (pinfunction "1_1") (pintype "passive"))
    )
    (net (code "82") (name "Net-(MCP23017_2-GPA1)") (class "Default")
      (node (ref "MCP23017_2") (pin "22") (pinfunction "GPA1_22") (pintype "bidirectional"))
      (node (ref "R5") (pin "1") (pinfunction "1_1") (pintype "passive"))
    )
    (net (code "83") (name "Net-(MCP23017_2-GPA2)") (class "Default")
      (node (ref "MCP23017_2") (pin "23") (pinfunction "GPA2_23") (pintype "bidirectional"))
      (node (ref "R6") (pin "1") (pinfunction "1_1") (pintype "passive"))
    )
    (net (code "84") (name "Net-(MCP23017_2-GPA3)") (class "Default")
      (node (ref "MCP23017_2") (pin "24") (pinfunction "GPA3_24") (pintype "bidirectional"))
      (node (ref "R7") (pin "1") (pinfunction "1_1") (pintype "passive"))
    )
    (net (code "85") (name "Net-(MCP23017_2-GPA4)") (class "Default")
      (node (ref "MCP23017_2") (pin "25") (pinfunction "GPA4_25") (pintype "bidirectional"))
      (node (ref "R8") (pin "1") (pinfunction "1_1") (pintype "passive"))
    )
    (net (code "86") (name "Net-(MCP23017_2-GPA5)") (class "Default")
      (node (ref "MCP23017_2") (pin "26") (pinfunction "GPA5_26") (pintype "bidirectional"))
      (node (ref "R9") (pin "1") (pinfunction "1_1") (pintype "passive"))
    )
    (net (code "87") (name "Net-(MCP23017_2-GPA6)") (class "Default")
      (node (ref "MCP23017_2") (pin "27") (pinfunction "GPA6_27") (pintype "bidirectional"))
      (node (ref "R10") (pin "1") (pinfunction "1_1") (pintype "passive"))
    )
    (net (code "88") (name "Net-(MCP23017_2-GPA7)") (class "Default")
      (node (ref "MCP23017_2") (pin "28") (pinfunction "GPA7_28") (pintype "bidirectional"))
      (node (ref "R11") (pin "1") (pinfunction "1_1") (pintype "passive"))
    )
    (net (code "89") (name "Net-(MCP23017_2-GPB0)") (class "Default")
      (node (ref "MCP23017_2") (pin "1") (pinfunction "GPB0_1") (pintype "bidirectional"))
      (node (ref "R1") (pin "1") (pinfunction "1_1") (pintype "passive"))
    )
    (net (code "90") (name "Net-(MCP23017_2-GPB1)") (class "Default")
      (node (ref "MCP23017_2") (pin "2") (pinfunction "GPB1_2") (pintype "bidirectional"))
      (node (ref "R2") (pin "1") (pinfunction "1_1") (pintype "passive"))
    )
    (net (code "91") (name "Net-(MCP23017_2-GPB2)") (class "Default")
      (node (ref "MCP23017_2") (pin "3") (pinfunction "GPB2_3") (pintype "bidirectional"))
      (node (ref "R3") (pin "1") (pinfunction "1_1") (pintype "passive"))
    )
    (net (code "92") (name "Net-(MCP23017_2-GPB7)") (class "Default")
      (node (ref "MCP23017_2") (pin "8") (pinfunction "GPB7_8") (pintype "bidirectional"))
      (node (ref "R12") (pin "1") (pinfunction "1_1") (pintype "passive"))
    )
    (net (code "93") (name "Net-(MCP23017_2-~{RESET})") (class "Default")
      (node (ref "MCP23017_2") (pin "18") (pinfunction "~{RESET}_18") (pintype "input"))
      (node (ref "R34") (pin "2") (pinfunction "2_2") (pintype "passive"))
    )
    (net (code "94") (name "unconnected-(ADX345--1-PadA1)") (class "Default")
      (node (ref "ADX345") (pin "A1") (pinfunction "-1_A1") (pintype "passive"))
    )
    (net (code "95") (name "unconnected-(ADX345--2-PadA2)") (class "Default")
      (node (ref "ADX345") (pin "A2") (pinfunction "-2_A2") (pintype "passive"))
    )
    (net (code "96") (name "unconnected-(ADX345--3-PadA3)") (class "Default")
      (node (ref "ADX345") (pin "A3") (pinfunction "-3_A3") (pintype "passive"))
    )
    (net (code "97") (name "unconnected-(ADX345--4-PadA4)") (class "Default")
      (node (ref "ADX345") (pin "A4") (pinfunction "-4_A4") (pintype "passive"))
    )
    (net (code "98") (name "unconnected-(FRISCHWASSERTANK--1-PadA1)") (class "Default")
      (node (ref "FRISCHWASSERTANK") (pin "A1") (pinfunction "-1_A1") (pintype "passive"))
    )
    (net (code "99") (name "unconnected-(FRISCHWASSERTANK--2-PadA2)") (class "Default")
      (node (ref "FRISCHWASSERTANK") (pin "A2") (pinfunction "-2_A2") (pintype "passive"))
    )
    (net (code "100") (name "unconnected-(FRISCHWASSERTANK--3-PadA3)") (class "Default")
      (node (ref "FRISCHWASSERTANK") (pin "A3") (pinfunction "-3_A3") (pintype "passive"))
    )
    (net (code "101") (name "unconnected-(FRISCHWASSERTANK--4-PadA4)") (class "Default")
      (node (ref "FRISCHWASSERTANK") (pin "A4") (pinfunction "-4_A4") (pintype "passive"))
    )
    (net (code "102") (name "unconnected-(FRISCHWASSERTANK--5-PadA5)") (class "Default")
      (node (ref "FRISCHWASSERTANK") (pin "A5") (pinfunction "-5_A5") (pintype "passive"))
    )
    (net (code "103") (name "unconnected-(FRISCHWASSERTANK--6-PadA6)") (class "Default")
      (node (ref "FRISCHWASSERTANK") (pin "A6") (pinfunction "-6_A6") (pintype "passive"))
    )
    (net (code "104") (name "unconnected-(FRISCHWASSERTANK--7-PadA7)") (class "Default")
      (node (ref "FRISCHWASSERTANK") (pin "A7") (pinfunction "-7_A7") (pintype "passive"))
    )
    (net (code "105") (name "unconnected-(FRISCHWASSERTANK--8-PadA8)") (class "Default")
      (node (ref "FRISCHWASSERTANK") (pin "A8") (pinfunction "-8_A8") (pintype "passive"))
    )
    (net (code "106") (name "unconnected-(FÄKALIENTANK--1-PadA1)") (class "Default")
      (node (ref "FÄKALIENTANK") (pin "A1") (pinfunction "-1_A1") (pintype "passive"))
    )
    (net (code "107") (name "unconnected-(FÄKALIENTANK--2-PadA2)") (class "Default")
      (node (ref "FÄKALIENTANK") (pin "A2") (pinfunction "-2_A2") (pintype "passive"))
    )
    (net (code "108") (name "unconnected-(FÄKALIENTANK--3-PadA3)") (class "Default")
      (node (ref "FÄKALIENTANK") (pin "A3") (pinfunction "-3_A3") (pintype "passive"))
    )
    (net (code "109") (name "unconnected-(FÄKALIENTANK--4-PadA4)") (class "Default")
      (node (ref "FÄKALIENTANK") (pin "A4") (pinfunction "-4_A4") (pintype "passive"))
    )
    (net (code "110") (name "unconnected-(FÄKALIENTANK--5-PadA5)") (class "Default")
      (node (ref "FÄKALIENTANK") (pin "A5") (pinfunction "-5_A5") (pintype "passive"))
    )
    (net (code "111") (name "unconnected-(FÄKALIENTANK--6-PadA6)") (class "Default")
      (node (ref "FÄKALIENTANK") (pin "A6") (pinfunction "-6_A6") (pintype "passive"))
    )
    (net (code "112") (name "unconnected-(FÄKALIENTANK--7-PadA7)") (class "Default")
      (node (ref "FÄKALIENTANK") (pin "A7") (pinfunction "-7_A7") (pintype "passive"))
    )
    (net (code "113") (name "unconnected-(FÄKALIENTANK--8-PadA8)") (class "Default")
      (node (ref "FÄKALIENTANK") (pin "A8") (pinfunction "-8_A8") (pintype "passive"))
    )
    (net (code "114") (name "unconnected-(FÄKALIENTANK-B-7-PadB7)") (class "Default")
      (node (ref "FÄKALIENTANK") (pin "B7") (pinfunction "B-7_B7") (pintype "passive"))
    )
    (net (code "115") (name "unconnected-(FÄKALIENTANK-B-8-PadB8)") (class "Default")
      (node (ref "FÄKALIENTANK") (pin "B8") (pinfunction "B-8_B8") (pintype "passive"))
    )
    (net (code "116") (name "unconnected-(GASWAAGE--1-PadA1)") (class "Default")
      (node (ref "GASWAAGE") (pin "A1") (pinfunction "-1_A1") (pintype "passive"))
    )
    (net (code "117") (name "unconnected-(GASWAAGE--2-PadA2)") (class "Default")
      (node (ref "GASWAAGE") (pin "A2") (pinfunction "-2_A2") (pintype "passive"))
    )
    (net (code "118") (name "unconnected-(GASWAAGE--3-PadA3)") (class "Default")
      (node (ref "GASWAAGE") (pin "A3") (pinfunction "-3_A3") (pintype "passive"))
    )
    (net (code "119") (name "unconnected-(GASWAAGE--4-PadA4)") (class "Default")
      (node (ref "GASWAAGE") (pin "A4") (pinfunction "-4_A4") (pintype "passive"))
    )
    (net (code "120") (name "unconnected-(GEHÄUSEDECKEL-Pad4)") (class "Default")
      (node (ref "GEHÄUSEDECKEL") (pin "4") (pinfunction "4_4") (pintype "passive"))
    )
    (net (code "121") (name "unconnected-(GEHÄUSEDECKEL-Pad6)") (class "Default")
      (node (ref "GEHÄUSEDECKEL") (pin "6") (pinfunction "6_6") (pintype "passive"))
    )
    (net (code "122") (name "unconnected-(GEHÄUSEDECKEL-Pad8)") (class "Default")
      (node (ref "GEHÄUSEDECKEL") (pin "8") (pinfunction "8_8") (pintype "passive"))
    )
    (net (code "123") (name "unconnected-(GEHÄUSEDECKEL-Pad10)") (class "Default")
      (node (ref "GEHÄUSEDECKEL") (pin "10") (pinfunction "10_10") (pintype "passive"))
    )
    (net (code "124") (name "unconnected-(GEHÄUSEDECKEL-Pad12)") (class "Default")
      (node (ref "GEHÄUSEDECKEL") (pin "12") (pinfunction "12_12") (pintype "passive"))
    )
    (net (code "125") (name "unconnected-(GPIO_EXTENSION--1-PadA1)") (class "Default")
      (node (ref "GPIO_EXTENSION") (pin "A1") (pinfunction "-1_A1") (pintype "passive"))
    )
    (net (code "126") (name "unconnected-(GPIO_EXTENSION--2-PadA2)") (class "Default")
      (node (ref "GPIO_EXTENSION") (pin "A2") (pinfunction "-2_A2") (pintype "passive"))
    )
    (net (code "127") (name "unconnected-(GPIO_EXTENSION--3-PadA3)") (class "Default")
      (node (ref "GPIO_EXTENSION") (pin "A3") (pinfunction "-3_A3") (pintype "passive"))
    )
    (net (code "128") (name "unconnected-(GPIO_EXTENSION--4-PadA4)") (class "Default")
      (node (ref "GPIO_EXTENSION") (pin "A4") (pinfunction "-4_A4") (pintype "passive"))
    )
    (net (code "129") (name "unconnected-(GPIO_EXTENSION--5-PadA5)") (class "Default")
      (node (ref "GPIO_EXTENSION") (pin "A5") (pinfunction "-5_A5") (pintype "passive"))
    )
    (net (code "130") (name "unconnected-(GPIO_EXTENSION--6-PadA6)") (class "Default")
      (node (ref "GPIO_EXTENSION") (pin "A6") (pinfunction "-6_A6") (pintype "passive"))
    )
    (net (code "131") (name "unconnected-(GPIO_EXTENSION--7-PadA7)") (class "Default")
      (node (ref "GPIO_EXTENSION") (pin "A7") (pinfunction "-7_A7") (pintype "passive"))
    )
    (net (code "132") (name "unconnected-(GPIO_EXTENSION--8-PadA8)") (class "Default")
      (node (ref "GPIO_EXTENSION") (pin "A8") (pinfunction "-8_A8") (pintype "passive"))
    )
    (net (code "133") (name "unconnected-(GPIO_EXTENSION--9-PadA9)") (class "Default")
      (node (ref "GPIO_EXTENSION") (pin "A9") (pinfunction "-9_A9") (pintype "passive"))
    )
    (net (code "134") (name "unconnected-(GPIO_EXTENSION--10-PadA10)") (class "Default")
      (node (ref "GPIO_EXTENSION") (pin "A10") (pinfunction "-10_A10") (pintype "passive"))
    )
    (net (code "135") (name "unconnected-(GPIO_EXTENSION--11-PadA11)") (class "Default")
      (node (ref "GPIO_EXTENSION") (pin "A11") (pinfunction "-11_A11") (pintype "passive"))
    )
    (net (code "136") (name "unconnected-(GPIO_EXTENSION--12-PadA12)") (class "Default")
      (node (ref "GPIO_EXTENSION") (pin "A12") (pinfunction "-12_A12") (pintype "passive"))
    )
    (net (code "137") (name "unconnected-(GPIO_EXTENSION--13-PadA13)") (class "Default")
      (node (ref "GPIO_EXTENSION") (pin "A13") (pinfunction "-13_A13") (pintype "passive"))
    )
    (net (code "138") (name "unconnected-(GPIO_EXTENSION--14-PadA14)") (class "Default")
      (node (ref "GPIO_EXTENSION") (pin "A14") (pinfunction "-14_A14") (pintype "passive"))
    )
    (net (code "139") (name "unconnected-(GPIO_EXTENSION--15-PadA15)") (class "Default")
      (node (ref "GPIO_EXTENSION") (pin "A15") (pinfunction "-15_A15") (pintype "passive"))
    )
    (net (code "140") (name "unconnected-(GPIO_EXTENSION--16-PadA16)") (class "Default")
      (node (ref "GPIO_EXTENSION") (pin "A16") (pinfunction "-16_A16") (pintype "passive"))
    )
    (net (code "141") (name "unconnected-(HX711-EXTERN--1-PadA1)") (class "Default")
      (node (ref "HX711-EXTERN") (pin "A1") (pinfunction "-1_A1") (pintype "passive"))
    )
    (net (code "142") (name "unconnected-(HX711-EXTERN--2-PadA2)") (class "Default")
      (node (ref "HX711-EXTERN") (pin "A2") (pinfunction "-2_A2") (pintype "passive"))
    )
    (net (code "143") (name "unconnected-(HX711-EXTERN--3-PadA3)") (class "Default")
      (node (ref "HX711-EXTERN") (pin "A3") (pinfunction "-3_A3") (pintype "passive"))
    )
    (net (code "144") (name "unconnected-(HX711-EXTERN--4-PadA4)") (class "Default")
      (node (ref "HX711-EXTERN") (pin "A4") (pinfunction "-4_A4") (pintype "passive"))
    )
    (net (code "145") (name "unconnected-(HX711-PadB+)") (class "Default")
      (node (ref "HX711") (pin "B+") (pinfunction "B+_B+") (pintype "bidirectional"))
    )
    (net (code "146") (name "unconnected-(HX711-PadB-)") (class "Default")
      (node (ref "HX711") (pin "B-") (pinfunction "B-_B-") (pintype "bidirectional"))
    )
    (net (code "147") (name "unconnected-(I2C-EXTENSION-Pad2)") (class "Default")
      (node (ref "I2C-EXTENSION") (pin "2") (pinfunction "2_2") (pintype "passive"))
    )
    (net (code "148") (name "unconnected-(I2C-EXTENSION-Pad4)") (class "Default")
      (node (ref "I2C-EXTENSION") (pin "4") (pinfunction "4_4") (pintype "passive"))
    )
    (net (code "149") (name "unconnected-(I2C-EXTENSION-Pad6)") (class "Default")
      (node (ref "I2C-EXTENSION") (pin "6") (pinfunction "6_6") (pintype "passive"))
    )
    (net (code "150") (name "unconnected-(I2C-EXTENSION-Pad7)") (class "Default")
      (node (ref "I2C-EXTENSION") (pin "7") (pinfunction "7_7") (pintype "passive"))
    )
    (net (code "151") (name "unconnected-(I2C-EXTENSION-Pad8)") (class "Default")
      (node (ref "I2C-EXTENSION") (pin "8") (pinfunction "8_8") (pintype "passive"))
    )
    (net (code "152") (name "unconnected-(I2CEXTENDER1-N.C.-Pad5)") (class "Default")
      (node (ref "I2CEXTENDER1") (pin "5") (pinfunction "N.C._5") (pintype "no_connect"))
    )
    (net (code "153") (name "unconnected-(I2CEXTENDER1-N.C._2-Pad1)") (class "Default")
      (node (ref "I2CEXTENDER1") (pin "1") (pinfunction "N.C._2_1") (pintype "no_connect"))
    )
    (net (code "154") (name "unconnected-(I2CEXTENDER2-N.C.-Pad5)") (class "Default")
      (node (ref "I2CEXTENDER2") (pin "5") (pinfunction "N.C._5") (pintype "no_connect"))
    )
    (net (code "155") (name "unconnected-(I2CEXTENDER2-N.C._2-Pad1)") (class "Default")
      (node (ref "I2CEXTENDER2") (pin "1") (pinfunction "N.C._2_1") (pintype "no_connect"))
    )
    (net (code "156") (name "unconnected-(KLIMA1--1-PadA1)") (class "Default")
      (node (ref "KLIMA1") (pin "A1") (pinfunction "-1_A1") (pintype "passive"))
    )
    (net (code "157") (name "unconnected-(KLIMA1--2-PadA2)") (class "Default")
      (node (ref "KLIMA1") (pin "A2") (pinfunction "-2_A2") (pintype "passive"))
    )
    (net (code "158") (name "unconnected-(KLIMA1--3-PadA3)") (class "Default")
      (node (ref "KLIMA1") (pin "A3") (pinfunction "-3_A3") (pintype "passive"))
    )
    (net (code "159") (name "unconnected-(KLIMA1--4-PadA4)") (class "Default")
      (node (ref "KLIMA1") (pin "A4") (pinfunction "-4_A4") (pintype "passive"))
    )
    (net (code "160") (name "unconnected-(KLIMA2--1-PadA1)") (class "Default")
      (node (ref "KLIMA2") (pin "A1") (pinfunction "-1_A1") (pintype "passive"))
    )
    (net (code "161") (name "unconnected-(KLIMA2--2-PadA2)") (class "Default")
      (node (ref "KLIMA2") (pin "A2") (pinfunction "-2_A2") (pintype "passive"))
    )
    (net (code "162") (name "unconnected-(KLIMA2--3-PadA3)") (class "Default")
      (node (ref "KLIMA2") (pin "A3") (pinfunction "-3_A3") (pintype "passive"))
    )
    (net (code "163") (name "unconnected-(KLIMA2--4-PadA4)") (class "Default")
      (node (ref "KLIMA2") (pin "A4") (pinfunction "-4_A4") (pintype "passive"))
    )
    (net (code "164") (name "unconnected-(KüHLSCHR.--1-PadA1)") (class "Default")
      (node (ref "KüHLSCHR.") (pin "A1") (pinfunction "-1_A1") (pintype "passive"))
    )
    (net (code "165") (name "unconnected-(KüHLSCHR.--2-PadA2)") (class "Default")
      (node (ref "KüHLSCHR.") (pin "A2") (pinfunction "-2_A2") (pintype "passive"))
    )
    (net (code "166") (name "unconnected-(KüHLSCHR.--3-PadA3)") (class "Default")
      (node (ref "KüHLSCHR.") (pin "A3") (pinfunction "-3_A3") (pintype "passive"))
    )
    (net (code "167") (name "unconnected-(LED-HL--1-PadA1)") (class "Default")
      (node (ref "LED-HL") (pin "A1") (pinfunction "-1_A1") (pintype "passive"))
    )
    (net (code "168") (name "unconnected-(LED-HL--2-PadA2)") (class "Default")
      (node (ref "LED-HL") (pin "A2") (pinfunction "-2_A2") (pintype "passive"))
    )
    (net (code "169") (name "unconnected-(LED-HL--3-PadA3)") (class "Default")
      (node (ref "LED-HL") (pin "A3") (pinfunction "-3_A3") (pintype "passive"))
    )
    (net (code "170") (name "unconnected-(LED-HL--4-PadA4)") (class "Default")
      (node (ref "LED-HL") (pin "A4") (pinfunction "-4_A4") (pintype "passive"))
    )
    (net (code "171") (name "unconnected-(LED-HR--1-PadA1)") (class "Default")
      (node (ref "LED-HR") (pin "A1") (pinfunction "-1_A1") (pintype "passive"))
    )
    (net (code "172") (name "unconnected-(LED-HR--2-PadA2)") (class "Default")
      (node (ref "LED-HR") (pin "A2") (pinfunction "-2_A2") (pintype "passive"))
    )
    (net (code "173") (name "unconnected-(LED-HR--3-PadA3)") (class "Default")
      (node (ref "LED-HR") (pin "A3") (pinfunction "-3_A3") (pintype "passive"))
    )
    (net (code "174") (name "unconnected-(LED-HR--4-PadA4)") (class "Default")
      (node (ref "LED-HR") (pin "A4") (pinfunction "-4_A4") (pintype "passive"))
    )
    (net (code "175") (name "unconnected-(LED-VD--1-PadA1)") (class "Default")
      (node (ref "LED-VD") (pin "A1") (pinfunction "-1_A1") (pintype "passive"))
    )
    (net (code "176") (name "unconnected-(LED-VD--2-PadA2)") (class "Default")
      (node (ref "LED-VD") (pin "A2") (pinfunction "-2_A2") (pintype "passive"))
    )
    (net (code "177") (name "unconnected-(LED-VD--3-PadA3)") (class "Default")
      (node (ref "LED-VD") (pin "A3") (pinfunction "-3_A3") (pintype "passive"))
    )
    (net (code "178") (name "unconnected-(LED-VD--4-PadA4)") (class "Default")
      (node (ref "LED-VD") (pin "A4") (pinfunction "-4_A4") (pintype "passive"))
    )
    (net (code "179") (name "unconnected-(LED-VL--1-PadA1)") (class "Default")
      (node (ref "LED-VL") (pin "A1") (pinfunction "-1_A1") (pintype "passive"))
    )
    (net (code "180") (name "unconnected-(LED-VL--2-PadA2)") (class "Default")
      (node (ref "LED-VL") (pin "A2") (pinfunction "-2_A2") (pintype "passive"))
    )
    (net (code "181") (name "unconnected-(LED-VL--3-PadA3)") (class "Default")
      (node (ref "LED-VL") (pin "A3") (pinfunction "-3_A3") (pintype "passive"))
    )
    (net (code "182") (name "unconnected-(LED-VL--4-PadA4)") (class "Default")
      (node (ref "LED-VL") (pin "A4") (pinfunction "-4_A4") (pintype "passive"))
    )
    (net (code "183") (name "unconnected-(LED-VR--1-PadA1)") (class "Default")
      (node (ref "LED-VR") (pin "A1") (pinfunction "-1_A1") (pintype "passive"))
    )
    (net (code "184") (name "unconnected-(LED-VR--2-PadA2)") (class "Default")
      (node (ref "LED-VR") (pin "A2") (pinfunction "-2_A2") (pintype "passive"))
    )
    (net (code "185") (name "unconnected-(LED-VR--3-PadA3)") (class "Default")
      (node (ref "LED-VR") (pin "A3") (pinfunction "-3_A3") (pintype "passive"))
    )
    (net (code "186") (name "unconnected-(LED-VR--4-PadA4)") (class "Default")
      (node (ref "LED-VR") (pin "A4") (pinfunction "-4_A4") (pintype "passive"))
    )
    (net (code "187") (name "unconnected-(LED-ZL--1-PadA1)") (class "Default")
      (node (ref "LED-ZL") (pin "A1") (pinfunction "-1_A1") (pintype "passive"))
    )
    (net (code "188") (name "unconnected-(LED-ZL--2-PadA2)") (class "Default")
      (node (ref "LED-ZL") (pin "A2") (pinfunction "-2_A2") (pintype "passive"))
    )
    (net (code "189") (name "unconnected-(LED-ZL--3-PadA3)") (class "Default")
      (node (ref "LED-ZL") (pin "A3") (pinfunction "-3_A3") (pintype "passive"))
    )
    (net (code "190") (name "unconnected-(LED-ZL--4-PadA4)") (class "Default")
      (node (ref "LED-ZL") (pin "A4") (pinfunction "-4_A4") (pintype "passive"))
    )
    (net (code "191") (name "unconnected-(LED-ZR--1-PadA1)") (class "Default")
      (node (ref "LED-ZR") (pin "A1") (pinfunction "-1_A1") (pintype "passive"))
    )
    (net (code "192") (name "unconnected-(LED-ZR--2-PadA2)") (class "Default")
      (node (ref "LED-ZR") (pin "A2") (pinfunction "-2_A2") (pintype "passive"))
    )
    (net (code "193") (name "unconnected-(LED-ZR--3-PadA3)") (class "Default")
      (node (ref "LED-ZR") (pin "A3") (pinfunction "-3_A3") (pintype "passive"))
    )
    (net (code "194") (name "unconnected-(LED-ZR--4-PadA4)") (class "Default")
      (node (ref "LED-ZR") (pin "A4") (pinfunction "-4_A4") (pintype "passive"))
    )
    (net (code "195") (name "unconnected-(MCP23017_1-INTA-Pad20)") (class "Default")
      (node (ref "MCP23017_1") (pin "20") (pinfunction "INTA_20") (pintype "output"))
    )
    (net (code "196") (name "unconnected-(MCP23017_1-INTB-Pad19)") (class "Default")
      (node (ref "MCP23017_1") (pin "19") (pinfunction "INTB_19") (pintype "output"))
    )
    (net (code "197") (name "unconnected-(MCP23017_2-INTA-Pad20)") (class "Default")
      (node (ref "MCP23017_2") (pin "20") (pinfunction "INTA_20") (pintype "output"))
    )
    (net (code "198") (name "unconnected-(MCP23017_2-INTB-Pad19)") (class "Default")
      (node (ref "MCP23017_2") (pin "19") (pinfunction "INTB_19") (pintype "output"))
    )
    (net (code "199") (name "unconnected-(RADAR--1-PadA1)") (class "Default")
      (node (ref "RADAR") (pin "A1") (pinfunction "-1_A1") (pintype "passive"))
    )
    (net (code "200") (name "unconnected-(RADAR--2-PadA2)") (class "Default")
      (node (ref "RADAR") (pin "A2") (pinfunction "-2_A2") (pintype "passive"))
    )
    (net (code "201") (name "unconnected-(RADAR--3-PadA3)") (class "Default")
      (node (ref "RADAR") (pin "A3") (pinfunction "-3_A3") (pintype "passive"))
    )
    (net (code "202") (name "unconnected-(RASPBERRY-PI-Pad10)") (class "Default")
      (node (ref "RASPBERRY-PI") (pin "10") (pinfunction "10_10") (pintype "passive"))
    )
  )
)
